# PiDog.net
KiCad netlist of a schematic drawn in EAGLE
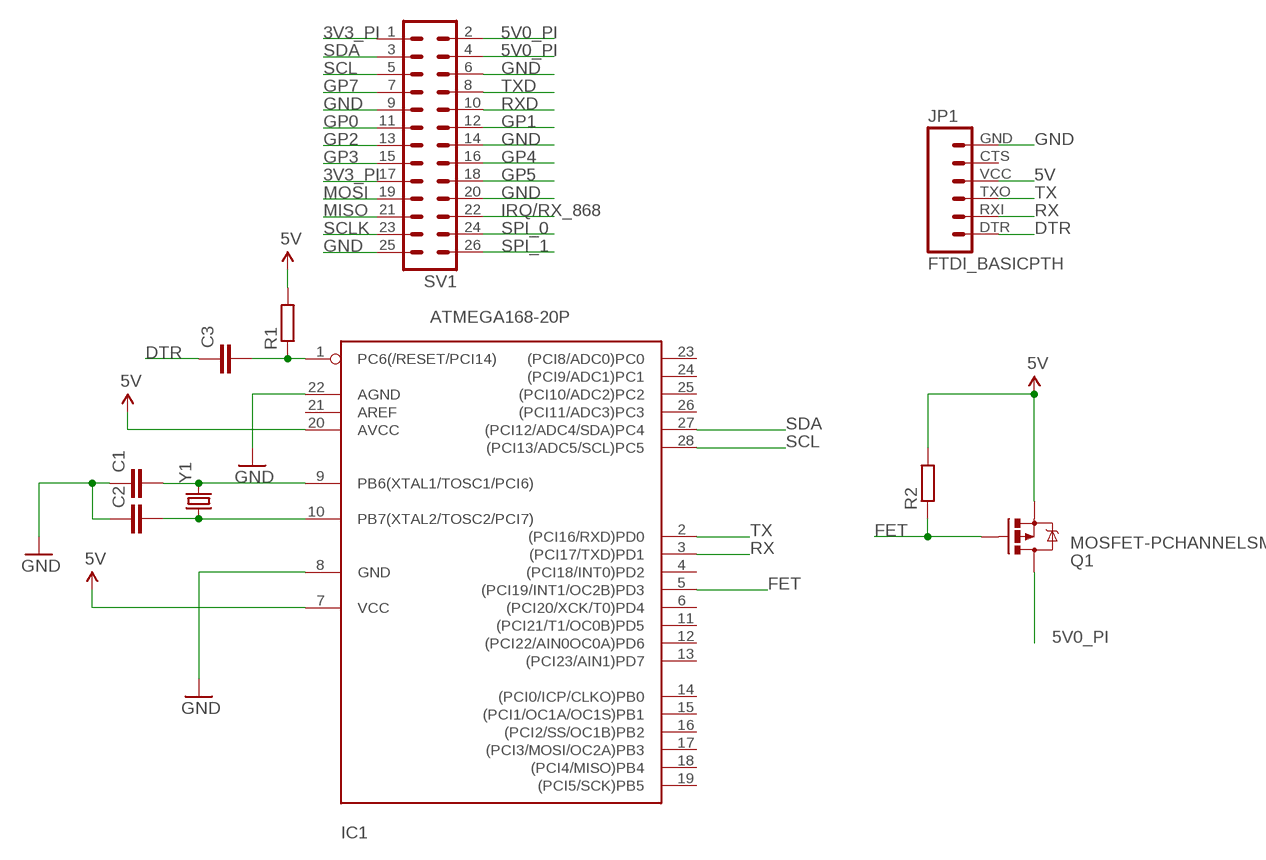
[diagram p0: schematic, sheet 1]

(export (version "E")
  (design (tool "Eeschema 10.0.6"))
  (components
    (comp (ref "C1")
      (value "C-EU025-030X050")
      (footprint "eagle-import:C025-030X050")
      (libsource (lib "eagle-import") (part "C-EU025-030X050"))
    )
    (comp (ref "C2")
      (value "C-EU025-030X050")
      (footprint "eagle-import:C025-030X050")
      (libsource (lib "eagle-import") (part "C-EU025-030X050"))
    )
    (comp (ref "C3")
      (value "C-EU025-030X050")
      (footprint "eagle-import:C025-030X050")
      (libsource (lib "eagle-import") (part "C-EU025-030X050"))
    )
    (comp (ref "IC1")
      (value "ATMEGA168-20P")
      (footprint "eagle-import:DIL28-3")
      (libsource (lib "eagle-import") (part "ATMEGA168P-20"))
    )
    (comp (ref "JP1")
      (value "FTDI_BASICPTH")
      (footprint "eagle-import:FTDI_BASIC")
      (libsource (lib "eagle-import") (part "FTDI_BASICPTH"))
    )
    (comp (ref "Q1")
      (value "MOSFET-PCHANNELSMD")
      (footprint "eagle-import:SOT23-3")
      (libsource (lib "eagle-import") (part "MOSFET-PCHANNELSMD"))
    )
    (comp (ref "R1")
      (value "R-EU_0603K-SMALL")
      (footprint "eagle-import:C0603K-SMALL")
      (libsource (lib "eagle-import") (part "R-EU_0603K-SMALL"))
    )
    (comp (ref "R2")
      (value "R-EU_0603K-SMALL")
      (footprint "eagle-import:C0603K-SMALL")
      (libsource (lib "eagle-import") (part "R-EU_0603K-SMALL"))
    )
    (comp (ref "SV1")
      (value "MA13-2-NO-SILK")
      (footprint "eagle-import:MA13-2-NS")
      (libsource (lib "eagle-import") (part "MA13-2-NO-SILK"))
    )
    (comp (ref "Y1")
      (value "CRYSTALHC49US")
      (footprint "eagle-import:HC49US")
      (libsource (lib "eagle-import") (part "CRYSTALHC49US"))
    )
  )
  (nets
    (net (code "1") (name "/3V3_PI") (class "Default")
      (node (ref "SV1") (pin "1") (pinfunction "1_1") (pintype "passive"))
      (node (ref "SV1") (pin "17") (pinfunction "17_17") (pintype "passive"))
    )
    (net (code "2") (name "/5V0_PI") (class "Default")
      (node (ref "Q1") (pin "3") (pinfunction "D_3") (pintype "passive"))
      (node (ref "SV1") (pin "2") (pinfunction "2_2") (pintype "passive"))
      (node (ref "SV1") (pin "4") (pinfunction "4_4") (pintype "passive"))
    )
    (net (code "3") (name "/DTR") (class "Default")
      (node (ref "C3") (pin "1") (pinfunction "1_1") (pintype "passive"))
      (node (ref "JP1") (pin "DTR") (pinfunction "1_DTR") (pintype "passive"))
    )
    (net (code "4") (name "/FET") (class "Default")
      (node (ref "IC1") (pin "5") (pinfunction "(PCI19/INT1/OC2B)PD3_5") (pintype "bidirectional"))
      (node (ref "Q1") (pin "1") (pinfunction "G_1") (pintype "passive"))
      (node (ref "R2") (pin "1") (pinfunction "1_1") (pintype "passive"))
    )
    (net (code "5") (name "/GP0") (class "Default")
      (node (ref "SV1") (pin "11") (pinfunction "11_11") (pintype "passive"))
    )
    (net (code "6") (name "/GP1") (class "Default")
      (node (ref "SV1") (pin "12") (pinfunction "12_12") (pintype "passive"))
    )
    (net (code "7") (name "/GP2") (class "Default")
      (node (ref "SV1") (pin "13") (pinfunction "13_13") (pintype "passive"))
    )
    (net (code "8") (name "/GP3") (class "Default")
      (node (ref "SV1") (pin "15") (pinfunction "15_15") (pintype "passive"))
    )
    (net (code "9") (name "/GP4") (class "Default")
      (node (ref "SV1") (pin "16") (pinfunction "16_16") (pintype "passive"))
    )
    (net (code "10") (name "/GP5") (class "Default")
      (node (ref "SV1") (pin "18") (pinfunction "18_18") (pintype "passive"))
    )
    (net (code "11") (name "/GP7") (class "Default")
      (node (ref "SV1") (pin "7") (pinfunction "7_7") (pintype "passive"))
    )
    (net (code "12") (name "/IRQ{slash}RX_868") (class "Default")
      (node (ref "SV1") (pin "22") (pinfunction "22_22") (pintype "passive"))
    )
    (net (code "13") (name "/MISO") (class "Default")
      (node (ref "SV1") (pin "21") (pinfunction "21_21") (pintype "passive"))
    )
    (net (code "14") (name "/MOSI") (class "Default")
      (node (ref "SV1") (pin "19") (pinfunction "19_19") (pintype "passive"))
    )
    (net (code "15") (name "/RX") (class "Default")
      (node (ref "IC1") (pin "3") (pinfunction "(PCI17/TXD)PD1_3") (pintype "bidirectional"))
      (node (ref "JP1") (pin "RXI") (pinfunction "2_RXI") (pintype "passive"))
    )
    (net (code "16") (name "/RXD") (class "Default")
      (node (ref "SV1") (pin "10") (pinfunction "10_10") (pintype "passive"))
    )
    (net (code "17") (name "/SCL") (class "Default")
      (node (ref "IC1") (pin "28") (pinfunction "(PCI13/ADC5/SCL)PC5_28") (pintype "bidirectional"))
      (node (ref "SV1") (pin "5") (pinfunction "5_5") (pintype "passive"))
    )
    (net (code "18") (name "/SCLK") (class "Default")
      (node (ref "SV1") (pin "23") (pinfunction "23_23") (pintype "passive"))
    )
    (net (code "19") (name "/SDA") (class "Default")
      (node (ref "IC1") (pin "27") (pinfunction "(PCI12/ADC4/SDA)PC4_27") (pintype "bidirectional"))
      (node (ref "SV1") (pin "3") (pinfunction "3_3") (pintype "passive"))
    )
    (net (code "20") (name "/SPI_0") (class "Default")
      (node (ref "SV1") (pin "24") (pinfunction "24_24") (pintype "passive"))
    )
    (net (code "21") (name "/SPI_1") (class "Default")
      (node (ref "SV1") (pin "26") (pinfunction "26_26") (pintype "passive"))
    )
    (net (code "22") (name "/TX") (class "Default")
      (node (ref "IC1") (pin "2") (pinfunction "(PCI16/RXD)PD0_2") (pintype "bidirectional"))
      (node (ref "JP1") (pin "TXO") (pinfunction "3_TXO") (pintype "passive"))
    )
    (net (code "23") (name "/TXD") (class "Default")
      (node (ref "SV1") (pin "8") (pinfunction "8_8") (pintype "passive"))
    )
    (net (code "24") (name "5V") (class "Default")
      (node (ref "IC1") (pin "20") (pinfunction "AVCC_20") (pintype "bidirectional"))
      (node (ref "IC1") (pin "7") (pinfunction "VCC_7") (pintype "bidirectional"))
      (node (ref "JP1") (pin "VCC") (pinfunction "4_VCC") (pintype "passive"))
      (node (ref "Q1") (pin "2") (pinfunction "S_2") (pintype "passive"))
      (node (ref "R1") (pin "2") (pinfunction "2_2") (pintype "passive"))
      (node (ref "R2") (pin "2") (pinfunction "2_2") (pintype "passive"))
    )
    (net (code "25") (name "GND") (class "Default")
      (node (ref "C1") (pin "1") (pinfunction "1_1") (pintype "passive"))
      (node (ref "C2") (pin "1") (pinfunction "1_1") (pintype "passive"))
      (node (ref "IC1") (pin "22") (pinfunction "AGND_22") (pintype "bidirectional"))
      (node (ref "IC1") (pin "8") (pinfunction "GND_8") (pintype "bidirectional"))
      (node (ref "JP1") (pin "GND") (pinfunction "6_GND") (pintype "passive"))
      (node (ref "SV1") (pin "14") (pinfunction "14_14") (pintype "passive"))
      (node (ref "SV1") (pin "20") (pinfunction "20_20") (pintype "passive"))
      (node (ref "SV1") (pin "25") (pinfunction "25_25") (pintype "passive"))
      (node (ref "SV1") (pin "6") (pinfunction "6_6") (pintype "passive"))
      (node (ref "SV1") (pin "9") (pinfunction "9_9") (pintype "passive"))
    )
    (net (code "26") (name "Net-(IC1-PB6(XTAL1{slash}TOSC1{slash}PCI6))") (class "Default")
      (node (ref "C1") (pin "2") (pinfunction "2_2") (pintype "passive"))
      (node (ref "IC1") (pin "9") (pinfunction "PB6(XTAL1/TOSC1/PCI6)_9") (pintype "bidirectional"))
      (node (ref "Y1") (pin "2") (pinfunction "2_2") (pintype "passive"))
    )
    (net (code "27") (name "Net-(IC1-PB7(XTAL2{slash}TOSC2{slash}PCI7))") (class "Default")
      (node (ref "C2") (pin "2") (pinfunction "2_2") (pintype "passive"))
      (node (ref "IC1") (pin "10") (pinfunction "PB7(XTAL2/TOSC2/PCI7)_10") (pintype "bidirectional"))
      (node (ref "Y1") (pin "1") (pinfunction "1_1") (pintype "passive"))
    )
    (net (code "28") (name "Net-(IC1-PC6({slash}RESET{slash}PCI14))") (class "Default")
      (node (ref "C3") (pin "2") (pinfunction "2_2") (pintype "passive"))
      (node (ref "IC1") (pin "1") (pinfunction "PC6(/RESET/PCI14)_1") (pintype "bidirectional"))
      (node (ref "R1") (pin "1") (pinfunction "1_1") (pintype "passive"))
    )
    (net (code "29") (name "unconnected-(IC1-(PCI0{slash}ICP{slash}CLKO)PB0-Pad14)") (class "Default")
      (node (ref "IC1") (pin "14") (pinfunction "(PCI0/ICP/CLKO)PB0_14") (pintype "bidirectional"))
    )
    (net (code "30") (name "unconnected-(IC1-(PCI1{slash}OC1A{slash}OC1S)PB1-Pad15)") (class "Default")
      (node (ref "IC1") (pin "15") (pinfunction "(PCI1/OC1A/OC1S)PB1_15") (pintype "bidirectional"))
    )
    (net (code "31") (name "unconnected-(IC1-(PCI2{slash}SS{slash}OC1B)PB2-Pad16)") (class "Default")
      (node (ref "IC1") (pin "16") (pinfunction "(PCI2/SS/OC1B)PB2_16") (pintype "bidirectional"))
    )
    (net (code "32") (name "unconnected-(IC1-(PCI3{slash}MOSI{slash}OC2A)PB3-Pad17)") (class "Default")
      (node (ref "IC1") (pin "17") (pinfunction "(PCI3/MOSI/OC2A)PB3_17") (pintype "bidirectional"))
    )
    (net (code "33") (name "unconnected-(IC1-(PCI4{slash}MISO)PB4-Pad18)") (class "Default")
      (node (ref "IC1") (pin "18") (pinfunction "(PCI4/MISO)PB4_18") (pintype "bidirectional"))
    )
    (net (code "34") (name "unconnected-(IC1-(PCI5{slash}SCK)PB5-Pad19)") (class "Default")
      (node (ref "IC1") (pin "19") (pinfunction "(PCI5/SCK)PB5_19") (pintype "bidirectional"))
    )
    (net (code "35") (name "unconnected-(IC1-(PCI8{slash}ADC0)PC0-Pad23)") (class "Default")
      (node (ref "IC1") (pin "23") (pinfunction "(PCI8/ADC0)PC0_23") (pintype "bidirectional"))
    )
    (net (code "36") (name "unconnected-(IC1-(PCI9{slash}ADC1)PC1-Pad24)") (class "Default")
      (node (ref "IC1") (pin "24") (pinfunction "(PCI9/ADC1)PC1_24") (pintype "bidirectional"))
    )
    (net (code "37") (name "unconnected-(IC1-(PCI10{slash}ADC2)PC2-Pad25)") (class "Default")
      (node (ref "IC1") (pin "25") (pinfunction "(PCI10/ADC2)PC2_25") (pintype "bidirectional"))
    )
    (net (code "38") (name "unconnected-(IC1-(PCI11{slash}ADC3)PC3-Pad26)") (class "Default")
      (node (ref "IC1") (pin "26") (pinfunction "(PCI11/ADC3)PC3_26") (pintype "bidirectional"))
    )
    (net (code "39") (name "unconnected-(IC1-(PCI18{slash}INT0)PD2-Pad4)") (class "Default")
      (node (ref "IC1") (pin "4") (pinfunction "(PCI18/INT0)PD2_4") (pintype "bidirectional"))
    )
    (net (code "40") (name "unconnected-(IC1-(PCI20{slash}XCK{slash}T0)PD4-Pad6)") (class "Default")
      (node (ref "IC1") (pin "6") (pinfunction "(PCI20/XCK/T0)PD4_6") (pintype "bidirectional"))
    )
    (net (code "41") (name "unconnected-(IC1-(PCI21{slash}T1{slash}OC0B)PD5-Pad11)") (class "Default")
      (node (ref "IC1") (pin "11") (pinfunction "(PCI21/T1/OC0B)PD5_11") (pintype "bidirectional"))
    )
    (net (code "42") (name "unconnected-(IC1-(PCI22{slash}AIN0OC0A)PD6-Pad12)") (class "Default")
      (node (ref "IC1") (pin "12") (pinfunction "(PCI22/AIN0OC0A)PD6_12") (pintype "bidirectional"))
    )
    (net (code "43") (name "unconnected-(IC1-(PCI23{slash}AIN1)PD7-Pad13)") (class "Default")
      (node (ref "IC1") (pin "13") (pinfunction "(PCI23/AIN1)PD7_13") (pintype "bidirectional"))
    )
    (net (code "44") (name "unconnected-(IC1-AREF-Pad21)") (class "Default")
      (node (ref "IC1") (pin "21") (pinfunction "AREF_21") (pintype "bidirectional"))
    )
    (net (code "45") (name "unconnected-(JP1-5-PadCTS)") (class "Default")
      (node (ref "JP1") (pin "CTS") (pinfunction "5_CTS") (pintype "passive"))
    )
  )
)
